# RPi_Extension_psu.net
KiCad netlist of a schematic drawn in EAGLE
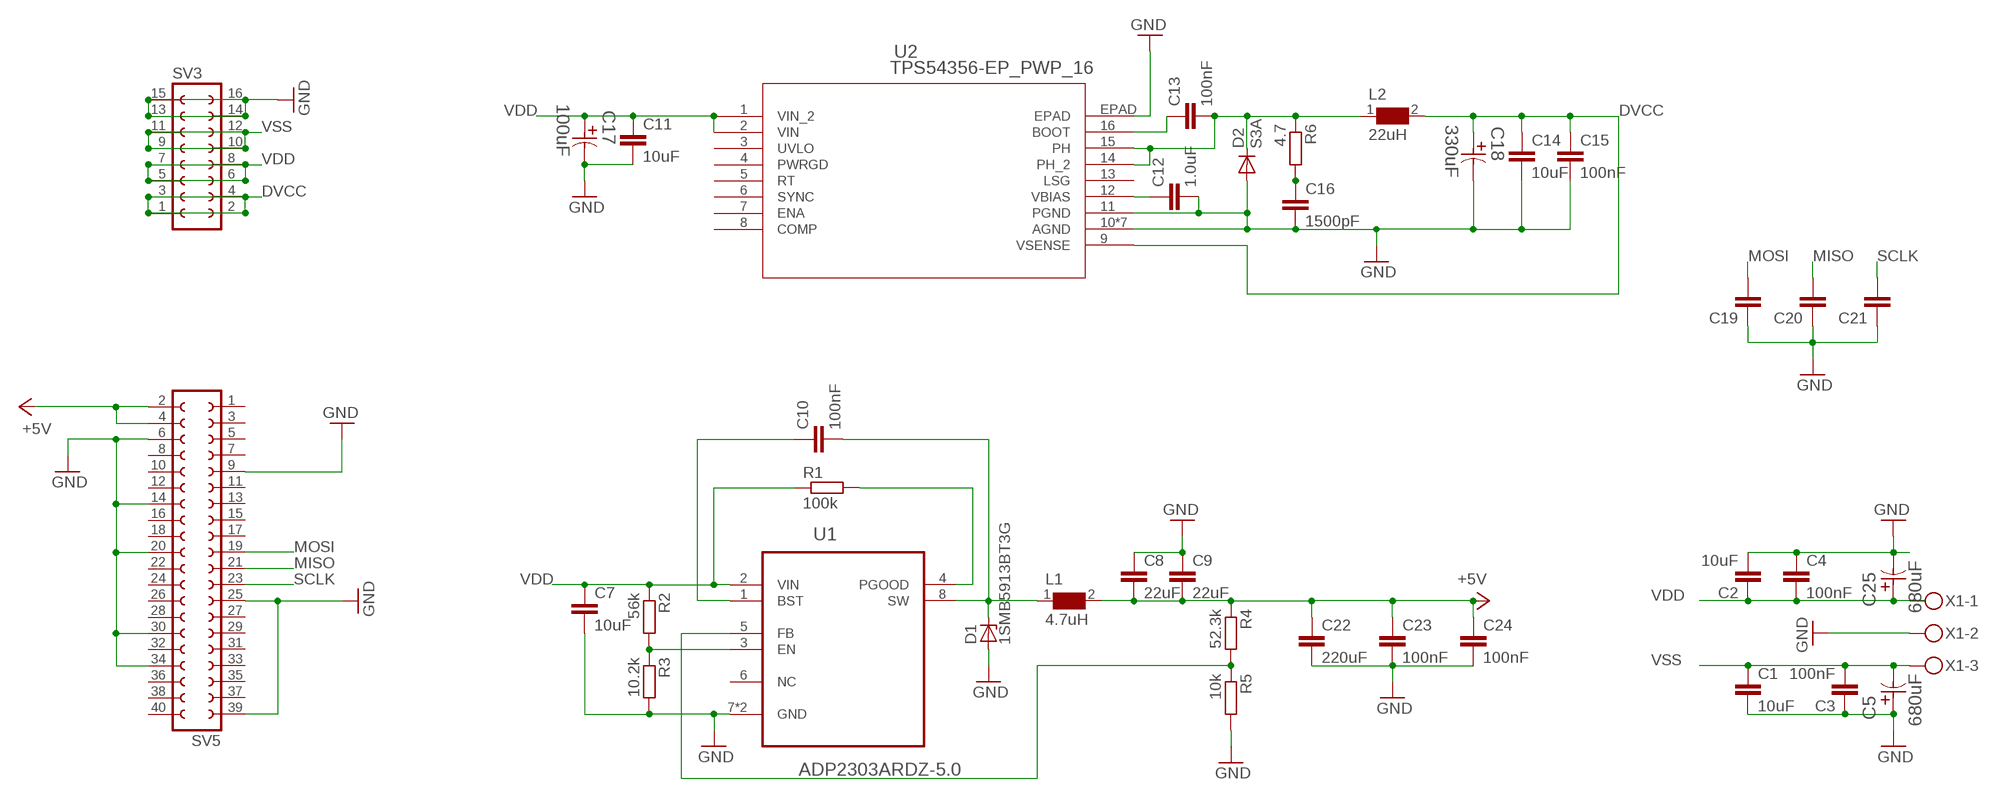
[diagram p0: schematic, sheet 1]

(export (version "E")
  (design (tool "Eeschema 10.0.6"))
  (components
    (comp (ref "C1")
      (value "10uF")
      (footprint "eagle-import:C1206")
      (libsource (lib "eagle-import") (part "C-EUC1206"))
    )
    (comp (ref "C2")
      (value "10uF")
      (footprint "eagle-import:C1206")
      (libsource (lib "eagle-import") (part "C-EUC1206"))
    )
    (comp (ref "C3")
      (value "100nF")
      (footprint "eagle-import:C0603")
      (libsource (lib "eagle-import") (part "C-EUC0603"))
    )
    (comp (ref "C4")
      (value "100nF")
      (footprint "eagle-import:C0603")
      (libsource (lib "eagle-import") (part "C-EUC0603"))
    )
    (comp (ref "C5")
      (value "680uF")
      (footprint "eagle-import:CAPAE830X1050N")
      (fields (field (name "MPN") "EEE-FT1C681AP") (field (name "TOLERANCE") "±20 %"))
      (libsource (lib "eagle-import") (part "EEE--CASE-FFT1C681AP"))
    )
    (comp (ref "C7")
      (value "10uF")
      (footprint "eagle-import:C0603")
      (libsource (lib "eagle-import") (part "C-EUC0603"))
    )
    (comp (ref "C8")
      (value "22uF")
      (footprint "eagle-import:C0603")
      (libsource (lib "eagle-import") (part "C-EUC0603"))
    )
    (comp (ref "C9")
      (value "22uF")
      (footprint "eagle-import:C0603")
      (libsource (lib "eagle-import") (part "C-EUC0603"))
    )
    (comp (ref "C10")
      (value "100nF")
      (footprint "eagle-import:C0603")
      (libsource (lib "eagle-import") (part "C-EUC0603"))
    )
    (comp (ref "C11")
      (value "10uF")
      (footprint "eagle-import:C0603")
      (libsource (lib "eagle-import") (part "C-EUC0603"))
    )
    (comp (ref "C12")
      (value "1.0uF")
      (footprint "eagle-import:C0603")
      (libsource (lib "eagle-import") (part "C-EUC0603"))
    )
    (comp (ref "C13")
      (value "100nF")
      (footprint "eagle-import:C0603")
      (libsource (lib "eagle-import") (part "C-EUC0603"))
    )
    (comp (ref "C14")
      (value "10uF")
      (footprint "eagle-import:C0603")
      (libsource (lib "eagle-import") (part "C-EUC0603"))
    )
    (comp (ref "C15")
      (value "100nF")
      (footprint "eagle-import:C0603")
      (libsource (lib "eagle-import") (part "C-EUC0603"))
    )
    (comp (ref "C16")
      (value "1500pF")
      (footprint "eagle-import:C0603")
      (libsource (lib "eagle-import") (part "C-EUC0603"))
    )
    (comp (ref "C17")
      (value "100uF")
      (footprint "eagle-import:CAPAE660X800N")
      (fields (field (name "MPN") "EEE-FK1V101XP") (field (name "TOLERANCE") "±20 %"))
      (libsource (lib "eagle-import") (part "EEE--CASE-D8FK1V101XP"))
    )
    (comp (ref "C18")
      (value "330uF")
      (footprint "eagle-import:CAPAE1030X1050N")
      (fields (field (name "MPN") "EEE-FK1V331P") (field (name "TOLERANCE") "±20 %"))
      (libsource (lib "eagle-import") (part "EEE--CASE-GFK1V331P"))
    )
    (comp (ref "C19")
      (value "C-EUC0603")
      (footprint "eagle-import:C0603")
      (libsource (lib "eagle-import") (part "C-EUC0603"))
    )
    (comp (ref "C20")
      (value "C-EUC0603")
      (footprint "eagle-import:C0603")
      (libsource (lib "eagle-import") (part "C-EUC0603"))
    )
    (comp (ref "C21")
      (value "C-EUC0603")
      (footprint "eagle-import:C0603")
      (libsource (lib "eagle-import") (part "C-EUC0603"))
    )
    (comp (ref "C22")
      (value "220uF")
      (footprint "eagle-import:C1206")
      (libsource (lib "eagle-import") (part "resistor_C-EUC1206"))
    )
    (comp (ref "C23")
      (value "100nF")
      (footprint "eagle-import:C0603")
      (libsource (lib "eagle-import") (part "C-EUC0603"))
    )
    (comp (ref "C24")
      (value "100nF")
      (footprint "eagle-import:C0603")
      (libsource (lib "eagle-import") (part "C-EUC0603"))
    )
    (comp (ref "C25")
      (value "680uF")
      (footprint "eagle-import:CAPAE830X1050N")
      (fields (field (name "MPN") "EEE-FT1C681AP") (field (name "TOLERANCE") "±20 %"))
      (libsource (lib "eagle-import") (part "EEE--CASE-FFT1C681AP"))
    )
    (comp (ref "D1")
      (value "1SMB5913BT3G")
      (footprint "eagle-import:DO214AA")
      (fields (field (name "MF") "ON Semiconductor"))
      (libsource (lib "eagle-import") (part "1SMB59BT3G13"))
    )
    (comp (ref "D2")
      (value "S3A")
      (footprint "eagle-import:DO214AB")
      (fields (field (name "MF") "Fairchild"))
      (libsource (lib "eagle-import") (part "S3A"))
    )
    (comp (ref "L1")
      (value "4.7uH")
      (footprint "eagle-import:WE-PD_1030_1050")
      (fields (field (name "MPN") "7447713047"))
      (libsource (lib "eagle-import") (part "WE-PD_1030/1050-7447713047"))
    )
    (comp (ref "L2")
      (value "22uH")
      (footprint "eagle-import:WE-PD_1260_1245_1280_1210")
      (fields (field (name "MPN") "744770122"))
      (libsource (lib "eagle-import") (part "WE-PD_1260/1245/1280/1210-744770122"))
    )
    (comp (ref "R1")
      (value "100k")
      (footprint "eagle-import:R0603")
      (libsource (lib "eagle-import") (part "R-EU_R0603"))
    )
    (comp (ref "R2")
      (value "56k")
      (footprint "eagle-import:R0603")
      (libsource (lib "eagle-import") (part "R-EU_R0603"))
    )
    (comp (ref "R3")
      (value "10.2k")
      (footprint "eagle-import:R0603")
      (libsource (lib "eagle-import") (part "R-EU_R0603"))
    )
    (comp (ref "R4")
      (value "52.3k")
      (footprint "eagle-import:R0603")
      (libsource (lib "eagle-import") (part "R-EU_R0603"))
    )
    (comp (ref "R5")
      (value "10k")
      (footprint "eagle-import:R0603")
      (libsource (lib "eagle-import") (part "R-EU_R0603"))
    )
    (comp (ref "R6")
      (value "4.7")
      (footprint "eagle-import:R0603")
      (libsource (lib "eagle-import") (part "R-EU_R0603"))
    )
    (comp (ref "SV3")
      (value "FE08-2")
      (footprint "eagle-import:FE08-2")
      (libsource (lib "eagle-import") (part "FE08-2"))
    )
    (comp (ref "SV5")
      (value "FE20-2")
      (footprint "eagle-import:FE20-2")
      (libsource (lib "eagle-import") (part "FE20-2"))
    )
    (comp (ref "U1")
      (value "ADP2303ARDZ-5.0")
      (footprint "eagle-import:SOIC127P600X175-9N")
      (libsource (lib "eagle-import") (part "ADP2303ARDZ-5.0"))
    )
    (comp (ref "U2")
      (value "TPS54356-EP_PWP_16")
      (footprint "eagle-import:PWP16_2P31X2P46")
      (fields
        (field (name "GENERIC_PART_NUMBER") "TPS54356-EP")
        (field (name "MANUFACTURER") "Texas Instruments")
        (field (name "MANUFACTURER_PART_NUMBER") "tps54356-ep_pwp_16")
      )
      (libsource (lib "eagle-import") (part "TPS54356-EP_PWP_16"))
    )
    (comp (ref "X1")
      (value "MKDSN1,5/3-5,08")
      (footprint "eagle-import:MKDSN1,5_3-5,08")
      (libsource (lib "eagle-import") (part "MKDSN1,5/3-5,08"))
    )
  )
  (nets
    (net (code "1") (name "+5V") (class "Default")
      (node (ref "C22") (pin "1") (pinfunction "1_1") (pintype "passive"))
      (node (ref "C23") (pin "1") (pinfunction "1_1") (pintype "passive"))
      (node (ref "C24") (pin "1") (pinfunction "1_1") (pintype "passive"))
      (node (ref "C8") (pin "2") (pinfunction "2_2") (pintype "passive"))
      (node (ref "C9") (pin "2") (pinfunction "2_2") (pintype "passive"))
      (node (ref "L1") (pin "2") (pinfunction "2_2") (pintype "passive"))
      (node (ref "R4") (pin "1") (pinfunction "1_1") (pintype "passive"))
      (node (ref "SV5") (pin "2") (pinfunction "2_2") (pintype "passive"))
      (node (ref "SV5") (pin "4") (pinfunction "4_4") (pintype "passive"))
    )
    (net (code "2") (name "/DVCC") (class "Default")
      (node (ref "C14") (pin "1") (pinfunction "1_1") (pintype "passive"))
      (node (ref "C15") (pin "1") (pinfunction "1_1") (pintype "passive"))
      (node (ref "C18") (pin "1") (pinfunction "1_1") (pintype "passive"))
      (node (ref "L2") (pin "2") (pinfunction "2_2") (pintype "passive"))
      (node (ref "SV3") (pin "1") (pinfunction "1_1") (pintype "passive"))
      (node (ref "SV3") (pin "2") (pinfunction "2_2") (pintype "passive"))
      (node (ref "SV3") (pin "3") (pinfunction "3_3") (pintype "passive"))
      (node (ref "SV3") (pin "4") (pinfunction "4_4") (pintype "passive"))
      (node (ref "U2") (pin "9") (pinfunction "VSENSE_9") (pintype "passive"))
    )
    (net (code "3") (name "/MISO") (class "Default")
      (node (ref "C20") (pin "2") (pinfunction "2_2") (pintype "passive"))
      (node (ref "SV5") (pin "21") (pinfunction "21_21") (pintype "passive"))
    )
    (net (code "4") (name "/MOSI") (class "Default")
      (node (ref "C19") (pin "2") (pinfunction "2_2") (pintype "passive"))
      (node (ref "SV5") (pin "19") (pinfunction "19_19") (pintype "passive"))
    )
    (net (code "5") (name "/PWRGD") (class "Default")
      (node (ref "U2") (pin "4") (pinfunction "PWRGD_4") (pintype "power_in"))
    )
    (net (code "6") (name "/SCLK") (class "Default")
      (node (ref "C21") (pin "2") (pinfunction "2_2") (pintype "passive"))
      (node (ref "SV5") (pin "23") (pinfunction "23_23") (pintype "passive"))
    )
    (net (code "7") (name "/VDD") (class "Default")
      (node (ref "C11") (pin "1") (pinfunction "1_1") (pintype "passive"))
      (node (ref "C17") (pin "1") (pinfunction "1_1") (pintype "passive"))
      (node (ref "C2") (pin "1") (pinfunction "1_1") (pintype "passive"))
      (node (ref "C25") (pin "1") (pinfunction "1_1") (pintype "passive"))
      (node (ref "C4") (pin "2") (pinfunction "2_2") (pintype "passive"))
      (node (ref "C7") (pin "1") (pinfunction "1_1") (pintype "passive"))
      (node (ref "R1") (pin "1") (pinfunction "1_1") (pintype "passive"))
      (node (ref "R2") (pin "1") (pinfunction "1_1") (pintype "passive"))
      (node (ref "SV3") (pin "5") (pinfunction "5_5") (pintype "passive"))
      (node (ref "SV3") (pin "6") (pinfunction "6_6") (pintype "passive"))
      (node (ref "SV3") (pin "7") (pinfunction "7_7") (pintype "passive"))
      (node (ref "SV3") (pin "8") (pinfunction "8_8") (pintype "passive"))
      (node (ref "U1") (pin "2") (pinfunction "VIN_2") (pintype "power_in"))
      (node (ref "U2") (pin "1") (pinfunction "VIN_2_1") (pintype "input"))
      (node (ref "U2") (pin "2") (pinfunction "VIN_2") (pintype "input"))
      (node (ref "X1") (pin "1") (pinfunction "KL_1") (pintype "passive"))
    )
    (net (code "8") (name "/VSS") (class "Default")
      (node (ref "C1") (pin "1") (pinfunction "1_1") (pintype "passive"))
      (node (ref "C3") (pin "2") (pinfunction "2_2") (pintype "passive"))
      (node (ref "C5") (pin "2") (pinfunction "2_2") (pintype "passive"))
      (node (ref "SV3") (pin "10") (pinfunction "10_10") (pintype "passive"))
      (node (ref "SV3") (pin "11") (pinfunction "11_11") (pintype "passive"))
      (node (ref "SV3") (pin "12") (pinfunction "12_12") (pintype "passive"))
      (node (ref "SV3") (pin "9") (pinfunction "9_9") (pintype "passive"))
      (node (ref "X1") (pin "3") (pinfunction "KL_3") (pintype "passive"))
    )
    (net (code "9") (name "GND") (class "Default")
      (node (ref "C1") (pin "2") (pinfunction "2_2") (pintype "passive"))
      (node (ref "C11") (pin "2") (pinfunction "2_2") (pintype "passive"))
      (node (ref "C12") (pin "2") (pinfunction "2_2") (pintype "passive"))
      (node (ref "C14") (pin "2") (pinfunction "2_2") (pintype "passive"))
      (node (ref "C15") (pin "2") (pinfunction "2_2") (pintype "passive"))
      (node (ref "C16") (pin "2") (pinfunction "2_2") (pintype "passive"))
      (node (ref "C17") (pin "2") (pinfunction "2_2") (pintype "passive"))
      (node (ref "C18") (pin "2") (pinfunction "2_2") (pintype "passive"))
      (node (ref "C19") (pin "1") (pinfunction "1_1") (pintype "passive"))
      (node (ref "C2") (pin "2") (pinfunction "2_2") (pintype "passive"))
      (node (ref "C20") (pin "1") (pinfunction "1_1") (pintype "passive"))
      (node (ref "C21") (pin "1") (pinfunction "1_1") (pintype "passive"))
      (node (ref "C22") (pin "2") (pinfunction "2_2") (pintype "passive"))
      (node (ref "C23") (pin "2") (pinfunction "2_2") (pintype "passive"))
      (node (ref "C24") (pin "2") (pinfunction "2_2") (pintype "passive"))
      (node (ref "C25") (pin "2") (pinfunction "2_2") (pintype "passive"))
      (node (ref "C3") (pin "1") (pinfunction "1_1") (pintype "passive"))
      (node (ref "C4") (pin "1") (pinfunction "1_1") (pintype "passive"))
      (node (ref "C5") (pin "1") (pinfunction "1_1") (pintype "passive"))
      (node (ref "C7") (pin "2") (pinfunction "2_2") (pintype "passive"))
      (node (ref "C8") (pin "1") (pinfunction "1_1") (pintype "passive"))
      (node (ref "C9") (pin "1") (pinfunction "1_1") (pintype "passive"))
      (node (ref "D1") (pin "A") (pinfunction "A_A") (pintype "passive"))
      (node (ref "D2") (pin "A") (pinfunction "A_A") (pintype "passive"))
      (node (ref "R3") (pin "2") (pinfunction "2_2") (pintype "passive"))
      (node (ref "R5") (pin "2") (pinfunction "2_2") (pintype "passive"))
      (node (ref "SV3") (pin "13") (pinfunction "13_13") (pintype "passive"))
      (node (ref "SV3") (pin "14") (pinfunction "14_14") (pintype "passive"))
      (node (ref "SV3") (pin "15") (pinfunction "15_15") (pintype "passive"))
      (node (ref "SV3") (pin "16") (pinfunction "16_16") (pintype "passive"))
      (node (ref "SV5") (pin "14") (pinfunction "14_14") (pintype "passive"))
      (node (ref "SV5") (pin "20") (pinfunction "20_20") (pintype "passive"))
      (node (ref "SV5") (pin "25") (pinfunction "25_25") (pintype "passive"))
      (node (ref "SV5") (pin "30") (pinfunction "30_30") (pintype "passive"))
      (node (ref "SV5") (pin "34") (pinfunction "34_34") (pintype "passive"))
      (node (ref "SV5") (pin "39") (pinfunction "39_39") (pintype "passive"))
      (node (ref "SV5") (pin "6") (pinfunction "6_6") (pintype "passive"))
      (node (ref "SV5") (pin "9") (pinfunction "9_9") (pintype "passive"))
      (node (ref "U1") (pin "7") (pinfunction "GND_7") (pintype "passive"))
      (node (ref "U1") (pin "9") (pinfunction "GND_9") (pintype "passive"))
      (node (ref "U2") (pin "10") (pinfunction "AGND_10") (pintype "power_in"))
      (node (ref "U2") (pin "11") (pinfunction "PGND_11") (pintype "power_in"))
      (node (ref "U2") (pin "EPAD") (pinfunction "EPAD_EPAD") (pintype "passive"))
      (node (ref "U2") (pin "V") (pinfunction "AGND_V") (pintype "power_in"))
      (node (ref "U2") (pin "V_1") (pinfunction "AGND_V_1") (pintype "power_in"))
      (node (ref "U2") (pin "V_2") (pinfunction "AGND_V_2") (pintype "power_in"))
      (node (ref "U2") (pin "V_3") (pinfunction "AGND_V_3") (pintype "power_in"))
      (node (ref "U2") (pin "V_4") (pinfunction "AGND_V_4") (pintype "power_in"))
      (node (ref "U2") (pin "V_5") (pinfunction "AGND_V_5") (pintype "power_in"))
      (node (ref "X1") (pin "2") (pinfunction "KL_2") (pintype "passive"))
    )
    (net (code "10") (name "Net-(C16-Pad1)") (class "Default")
      (node (ref "C16") (pin "1") (pinfunction "1_1") (pintype "passive"))
      (node (ref "R6") (pin "2") (pinfunction "2_2") (pintype "passive"))
    )
    (net (code "11") (name "Net-(U1-BST)") (class "Default")
      (node (ref "C10") (pin "1") (pinfunction "1_1") (pintype "passive"))
      (node (ref "U1") (pin "1") (pinfunction "BST_1") (pintype "power_in"))
    )
    (net (code "12") (name "Net-(U1-EN)") (class "Default")
      (node (ref "R2") (pin "2") (pinfunction "2_2") (pintype "passive"))
      (node (ref "R3") (pin "1") (pinfunction "1_1") (pintype "passive"))
      (node (ref "U1") (pin "3") (pinfunction "EN_3") (pintype "input"))
    )
    (net (code "13") (name "Net-(U1-FB)") (class "Default")
      (node (ref "R4") (pin "2") (pinfunction "2_2") (pintype "passive"))
      (node (ref "R5") (pin "1") (pinfunction "1_1") (pintype "passive"))
      (node (ref "U1") (pin "5") (pinfunction "FB_5") (pintype "input"))
    )
    (net (code "14") (name "Net-(U1-PGOOD)") (class "Default")
      (node (ref "R1") (pin "2") (pinfunction "2_2") (pintype "passive"))
      (node (ref "U1") (pin "4") (pinfunction "PGOOD_4") (pintype "output"))
    )
    (net (code "15") (name "Net-(U1-SW)") (class "Default")
      (node (ref "C10") (pin "2") (pinfunction "2_2") (pintype "passive"))
      (node (ref "D1") (pin "C") (pinfunction "C_C") (pintype "passive"))
      (node (ref "L1") (pin "1") (pinfunction "1_1") (pintype "passive"))
      (node (ref "U1") (pin "8") (pinfunction "SW_8") (pintype "output"))
    )
    (net (code "16") (name "Net-(U2-BOOT)") (class "Default")
      (node (ref "C13") (pin "1") (pinfunction "1_1") (pintype "passive"))
      (node (ref "U2") (pin "16") (pinfunction "BOOT_16") (pintype "passive"))
    )
    (net (code "17") (name "Net-(U2-PH)") (class "Default")
      (node (ref "C13") (pin "2") (pinfunction "2_2") (pintype "passive"))
      (node (ref "D2") (pin "C") (pinfunction "C_C") (pintype "passive"))
      (node (ref "L2") (pin "1") (pinfunction "1_1") (pintype "passive"))
      (node (ref "R6") (pin "1") (pinfunction "1_1") (pintype "passive"))
      (node (ref "U2") (pin "14") (pinfunction "PH_2_14") (pintype "passive"))
      (node (ref "U2") (pin "15") (pinfunction "PH_15") (pintype "passive"))
    )
    (net (code "18") (name "Net-(U2-VBIAS)") (class "Default")
      (node (ref "C12") (pin "1") (pinfunction "1_1") (pintype "passive"))
      (node (ref "U2") (pin "12") (pinfunction "VBIAS_12") (pintype "passive"))
    )
    (net (code "19") (name "unconnected-(SV5-Pad1)") (class "Default")
      (node (ref "SV5") (pin "1") (pinfunction "1_1") (pintype "passive"))
    )
    (net (code "20") (name "unconnected-(SV5-Pad3)") (class "Default")
      (node (ref "SV5") (pin "3") (pinfunction "3_3") (pintype "passive"))
    )
    (net (code "21") (name "unconnected-(SV5-Pad5)") (class "Default")
      (node (ref "SV5") (pin "5") (pinfunction "5_5") (pintype "passive"))
    )
    (net (code "22") (name "unconnected-(SV5-Pad7)") (class "Default")
      (node (ref "SV5") (pin "7") (pinfunction "7_7") (pintype "passive"))
    )
    (net (code "23") (name "unconnected-(SV5-Pad8)") (class "Default")
      (node (ref "SV5") (pin "8") (pinfunction "8_8") (pintype "passive"))
    )
    (net (code "24") (name "unconnected-(SV5-Pad10)") (class "Default")
      (node (ref "SV5") (pin "10") (pinfunction "10_10") (pintype "passive"))
    )
    (net (code "25") (name "unconnected-(SV5-Pad11)") (class "Default")
      (node (ref "SV5") (pin "11") (pinfunction "11_11") (pintype "passive"))
    )
    (net (code "26") (name "unconnected-(SV5-Pad12)") (class "Default")
      (node (ref "SV5") (pin "12") (pinfunction "12_12") (pintype "passive"))
    )
    (net (code "27") (name "unconnected-(SV5-Pad13)") (class "Default")
      (node (ref "SV5") (pin "13") (pinfunction "13_13") (pintype "passive"))
    )
    (net (code "28") (name "unconnected-(SV5-Pad15)") (class "Default")
      (node (ref "SV5") (pin "15") (pinfunction "15_15") (pintype "passive"))
    )
    (net (code "29") (name "unconnected-(SV5-Pad16)") (class "Default")
      (node (ref "SV5") (pin "16") (pinfunction "16_16") (pintype "passive"))
    )
    (net (code "30") (name "unconnected-(SV5-Pad17)") (class "Default")
      (node (ref "SV5") (pin "17") (pinfunction "17_17") (pintype "passive"))
    )
    (net (code "31") (name "unconnected-(SV5-Pad18)") (class "Default")
      (node (ref "SV5") (pin "18") (pinfunction "18_18") (pintype "passive"))
    )
    (net (code "32") (name "unconnected-(SV5-Pad22)") (class "Default")
      (node (ref "SV5") (pin "22") (pinfunction "22_22") (pintype "passive"))
    )
    (net (code "33") (name "unconnected-(SV5-Pad24)") (class "Default")
      (node (ref "SV5") (pin "24") (pinfunction "24_24") (pintype "passive"))
    )
    (net (code "34") (name "unconnected-(SV5-Pad26)") (class "Default")
      (node (ref "SV5") (pin "26") (pinfunction "26_26") (pintype "passive"))
    )
    (net (code "35") (name "unconnected-(SV5-Pad27)") (class "Default")
      (node (ref "SV5") (pin "27") (pinfunction "27_27") (pintype "passive"))
    )
    (net (code "36") (name "unconnected-(SV5-Pad28)") (class "Default")
      (node (ref "SV5") (pin "28") (pinfunction "28_28") (pintype "passive"))
    )
    (net (code "37") (name "unconnected-(SV5-Pad29)") (class "Default")
      (node (ref "SV5") (pin "29") (pinfunction "29_29") (pintype "passive"))
    )
    (net (code "38") (name "unconnected-(SV5-Pad31)") (class "Default")
      (node (ref "SV5") (pin "31") (pinfunction "31_31") (pintype "passive"))
    )
    (net (code "39") (name "unconnected-(SV5-Pad32)") (class "Default")
      (node (ref "SV5") (pin "32") (pinfunction "32_32") (pintype "passive"))
    )
    (net (code "40") (name "unconnected-(SV5-Pad33)") (class "Default")
      (node (ref "SV5") (pin "33") (pinfunction "33_33") (pintype "passive"))
    )
    (net (code "41") (name "unconnected-(SV5-Pad35)") (class "Default")
      (node (ref "SV5") (pin "35") (pinfunction "35_35") (pintype "passive"))
    )
    (net (code "42") (name "unconnected-(SV5-Pad36)") (class "Default")
      (node (ref "SV5") (pin "36") (pinfunction "36_36") (pintype "passive"))
    )
    (net (code "43") (name "unconnected-(SV5-Pad37)") (class "Default")
      (node (ref "SV5") (pin "37") (pinfunction "37_37") (pintype "passive"))
    )
    (net (code "44") (name "unconnected-(SV5-Pad38)") (class "Default")
      (node (ref "SV5") (pin "38") (pinfunction "38_38") (pintype "passive"))
    )
    (net (code "45") (name "unconnected-(SV5-Pad40)") (class "Default")
      (node (ref "SV5") (pin "40") (pinfunction "40_40") (pintype "passive"))
    )
    (net (code "46") (name "unconnected-(U1-NC-Pad6)") (class "Default")
      (node (ref "U1") (pin "6") (pinfunction "NC_6") (pintype "no_connect"))
    )
    (net (code "47") (name "unconnected-(U2-COMP-Pad8)") (class "Default")
      (node (ref "U2") (pin "8") (pinfunction "COMP_8") (pintype "output"))
    )
    (net (code "48") (name "unconnected-(U2-ENA-Pad7)") (class "Default")
      (node (ref "U2") (pin "7") (pinfunction "ENA_7") (pintype "passive"))
    )
    (net (code "49") (name "unconnected-(U2-LSG-Pad13)") (class "Default")
      (node (ref "U2") (pin "13") (pinfunction "LSG_13") (pintype "passive"))
    )
    (net (code "50") (name "unconnected-(U2-RT-Pad5)") (class "Default")
      (node (ref "U2") (pin "5") (pinfunction "RT_5") (pintype "passive"))
    )
    (net (code "51") (name "unconnected-(U2-SYNC-Pad6)") (class "Default")
      (node (ref "U2") (pin "6") (pinfunction "SYNC_6") (pintype "bidirectional"))
    )
    (net (code "52") (name "unconnected-(U2-UVLO-Pad3)") (class "Default")
      (node (ref "U2") (pin "3") (pinfunction "UVLO_3") (pintype "passive"))
    )
  )
)
